# InventHQ-LED-V1.net
KiCad netlist of a schematic drawn in EAGLE
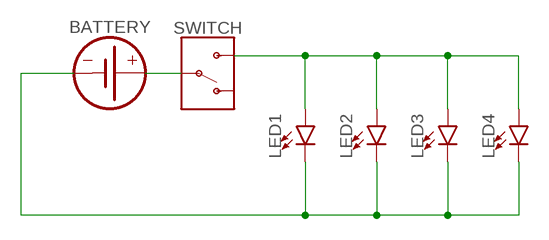
[diagram p0: schematic, sheet 1]

(export (version "E")
  (design (tool "Eeschema 10.0.6"))
  (components
    (comp (ref "BATTERY")
      (value "COIN_CELL_HOLDER_BH-25C-1")
      (footprint "eagle-import:BH-25C-1")
      (libsource (lib "eagle-import") (part "COIN_CELL_HOLDER_BH-25C-1"))
    )
    (comp (ref "LED1")
      (value "LED_5MM_MIKE")
      (footprint "eagle-import:LED_5MM_MIKE")
      (libsource (lib "eagle-import") (part "LED_5MM_MIKE"))
    )
    (comp (ref "LED2")
      (value "LED_5MM_MIKE")
      (footprint "eagle-import:LED_5MM_MIKE")
      (libsource (lib "eagle-import") (part "LED_5MM_MIKE"))
    )
    (comp (ref "LED3")
      (value "LED_5MM_MIKE")
      (footprint "eagle-import:LED_5MM_MIKE")
      (libsource (lib "eagle-import") (part "LED_5MM_MIKE"))
    )
    (comp (ref "LED4")
      (value "LED_5MM_MIKE")
      (footprint "eagle-import:LED_5MM_MIKE")
      (libsource (lib "eagle-import") (part "LED_5MM_MIKE"))
    )
    (comp (ref "SWITCH")
      (value "SWITCH-SPDT-PTH-11.6X4.0MM-KIT")
      (footprint "eagle-import:SWITCH_SPDT_PTH_11.6X4.0MM_KIT")
      (libsource (lib "eagle-import") (part "SWITCH-SPDT-PTH-11.6X4.0MM-KIT"))
    )
  )
  (nets
    (net (code "1") (name "Net-(BATTERY-+)") (class "Default")
      (node (ref "BATTERY") (pin "POS") (pinfunction "+_POS") (pintype "passive"))
      (node (ref "SWITCH") (pin "2") (pinfunction "P_2") (pintype "passive"))
    )
    (net (code "2") (name "Net-(BATTERY--)") (class "Default")
      (node (ref "BATTERY") (pin "NEG") (pinfunction "-_NEG") (pintype "passive"))
      (node (ref "LED1") (pin "K") (pinfunction "C_K") (pintype "passive"))
      (node (ref "LED2") (pin "K") (pinfunction "C_K") (pintype "passive"))
      (node (ref "LED3") (pin "K") (pinfunction "C_K") (pintype "passive"))
      (node (ref "LED4") (pin "K") (pinfunction "C_K") (pintype "passive"))
    )
    (net (code "3") (name "Net-(SWITCH-S)") (class "Default")
      (node (ref "LED1") (pin "A") (pinfunction "A_A") (pintype "passive"))
      (node (ref "LED2") (pin "A") (pinfunction "A_A") (pintype "passive"))
      (node (ref "LED3") (pin "A") (pinfunction "A_A") (pintype "passive"))
      (node (ref "LED4") (pin "A") (pinfunction "A_A") (pintype "passive"))
      (node (ref "SWITCH") (pin "3") (pinfunction "S_3") (pintype "passive"))
    )
    (net (code "4") (name "unconnected-(SWITCH-O-Pad1)") (class "Default")
      (node (ref "SWITCH") (pin "1") (pinfunction "O_1") (pintype "passive"))
    )
  )
)
